# Spare_Pins.net
KiCad netlist of a schematic drawn in Altium Designer
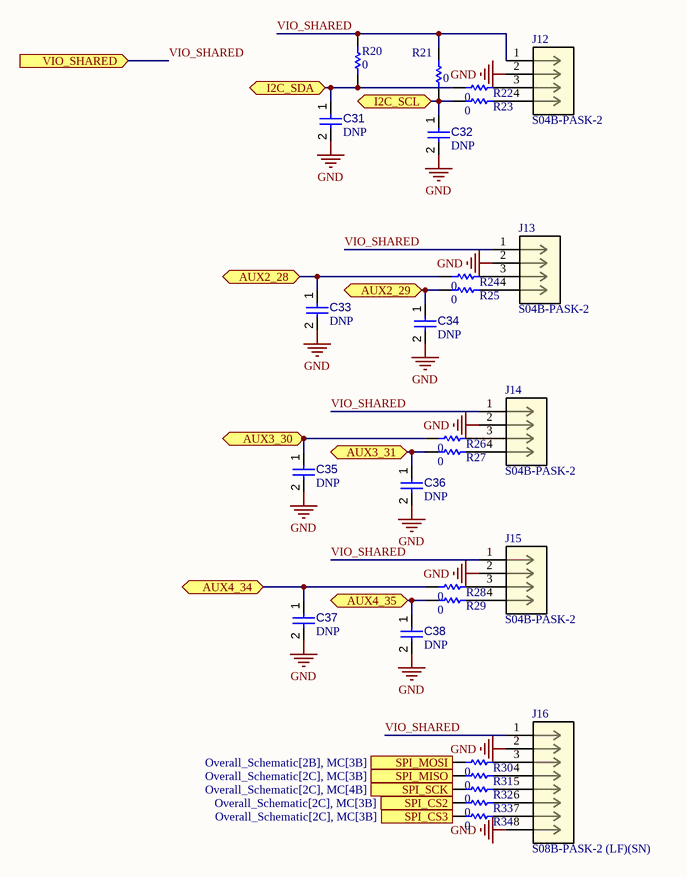
[diagram p0: Spare_Pins.SchDoc]

(export (version "E")
  (design (tool "Eeschema 10.0.6"))
  (components
    (comp (ref "C31")
      (value "DNP")
      (footprint "CAPC1608X90X40ML10T20")
      (description "0603 (1608 Metric)")
      (fields (field (name "TOLERANCE") "5%") (field (name "Comment") "DNP/placeholder"))
      (libsource (lib "Chen-Shi Liou") (part "CAP-NP-2"))
    )
    (comp (ref "C32")
      (value "DNP")
      (footprint "CAPC1608X90X40ML10T20")
      (description "0603 (1608 Metric)")
      (fields (field (name "TOLERANCE") "5%") (field (name "Comment") "DNP/placeholder"))
      (libsource (lib "Chen-Shi Liou") (part "CAP-NP-2"))
    )
    (comp (ref "C33")
      (value "DNP")
      (footprint "CAPC1608X90X40ML10T20")
      (description "0603 (1608 Metric)")
      (fields (field (name "TOLERANCE") "5%") (field (name "Comment") "DNP/placeholder"))
      (libsource (lib "Chen-Shi Liou") (part "CAP-NP-2"))
    )
    (comp (ref "C34")
      (value "DNP")
      (footprint "CAPC1608X90X40ML10T20")
      (description "0603 (1608 Metric)")
      (fields (field (name "TOLERANCE") "5%") (field (name "Comment") "DNP/placeholder"))
      (libsource (lib "Chen-Shi Liou") (part "CAP-NP-2"))
    )
    (comp (ref "C35")
      (value "DNP")
      (footprint "CAPC1608X90X40ML10T20")
      (description "0603 (1608 Metric)")
      (fields (field (name "TOLERANCE") "5%") (field (name "Comment") "DNP/placeholder"))
      (libsource (lib "Chen-Shi Liou") (part "CAP-NP-2"))
    )
    (comp (ref "C36")
      (value "DNP")
      (footprint "CAPC1608X90X40ML10T20")
      (description "0603 (1608 Metric)")
      (fields (field (name "TOLERANCE") "5%") (field (name "Comment") "DNP/placeholder"))
      (libsource (lib "Chen-Shi Liou") (part "CAP-NP-2"))
    )
    (comp (ref "C37")
      (value "DNP")
      (footprint "CAPC1608X90X40ML10T20")
      (description "0603 (1608 Metric)")
      (fields (field (name "TOLERANCE") "5%") (field (name "Comment") "DNP/placeholder"))
      (libsource (lib "Chen-Shi Liou") (part "CAP-NP-2"))
    )
    (comp (ref "C38")
      (value "DNP")
      (footprint "CAPC1608X90X40ML10T20")
      (description "0603 (1608 Metric)")
      (fields (field (name "TOLERANCE") "5%") (field (name "Comment") "DNP/placeholder"))
      (libsource (lib "Chen-Shi Liou") (part "CAP-NP-2"))
    )
    (comp (ref "J12")
      (value "S04B-PASK-2")
      (footprint "CONN4_S04B-PASK_JST")
      (description "Description")
      (fields (field (name "COPYRIGHT") "Copyright (C) 2025 Ultra Librarian. All rights reserved."))
      (libsource (lib "S04B-PASK-2") (part "S04B-PASK-2"))
    )
    (comp (ref "J13")
      (value "S04B-PASK-2")
      (footprint "CONN4_S04B-PASK_JST")
      (description "Description")
      (fields (field (name "COPYRIGHT") "Copyright (C) 2025 Ultra Librarian. All rights reserved."))
      (libsource (lib "S04B-PASK-2") (part "S04B-PASK-2"))
    )
    (comp (ref "J14")
      (value "S04B-PASK-2")
      (footprint "CONN4_S04B-PASK_JST")
      (description "Description")
      (fields (field (name "COPYRIGHT") "Copyright (C) 2025 Ultra Librarian. All rights reserved."))
      (libsource (lib "S04B-PASK-2") (part "S04B-PASK-2"))
    )
    (comp (ref "J15")
      (value "S04B-PASK-2")
      (footprint "CONN4_S04B-PASK_JST")
      (description "Description")
      (fields (field (name "COPYRIGHT") "Copyright (C) 2025 Ultra Librarian. All rights reserved."))
      (libsource (lib "S04B-PASK-2") (part "S04B-PASK-2"))
    )
    (comp (ref "J16")
      (value "S08B-PASK-2 (LF)(SN)")
      (footprint "CONN_S08B-PASK-2_JST")
      (description "Description")
      (fields (field (name "COPYRIGHT") "Copyright (C) 2026 Ultra Librarian. All rights reserved."))
      (libsource (lib "S08B-PASK-2LFSN") (part "S08B-PASK-2 LFSN"))
    )
    (comp (ref "R20")
      (value "0")
      (footprint "RESC1608X55X25ML10T15")
      (description "Chip Resistor, 0 Ohm, 0.1 W, -55 to 155 degC, 0603 (1608 Metric)")
      (fields (field (name "POWER") "100mW") (field (name "TOLERANCE") "5%"))
      (libsource (lib "Chen-Shi Liou") (part "RES-2"))
    )
    (comp (ref "R21")
      (value "0")
      (footprint "RESC1608X55X25ML10T15")
      (description "Chip Resistor, 0 Ohm, 0.1 W, -55 to 155 degC, 0603 (1608 Metric)")
      (fields (field (name "POWER") "100mW") (field (name "TOLERANCE") "5%"))
      (libsource (lib "Chen-Shi Liou") (part "RES-2"))
    )
    (comp (ref "R22")
      (value "0")
      (footprint "RESC1608X55X25ML10T15")
      (description "Chip Resistor, 0 Ohm, 0.1 W, -55 to 155 degC, 0603 (1608 Metric)")
      (fields (field (name "POWER") "100mW") (field (name "TOLERANCE") "5%"))
      (libsource (lib "Chen-Shi Liou") (part "RES-2"))
    )
    (comp (ref "R23")
      (value "0")
      (footprint "RESC1608X55X25ML10T15")
      (description "Chip Resistor, 0 Ohm, 0.1 W, -55 to 155 degC, 0603 (1608 Metric)")
      (fields (field (name "POWER") "100mW") (field (name "TOLERANCE") "5%"))
      (libsource (lib "Chen-Shi Liou") (part "RES-2"))
    )
    (comp (ref "R24")
      (value "0")
      (footprint "RESC1608X55X25ML10T15")
      (description "Chip Resistor, 0 Ohm, 0.1 W, -55 to 155 degC, 0603 (1608 Metric)")
      (fields (field (name "POWER") "100mW") (field (name "TOLERANCE") "5%"))
      (libsource (lib "Chen-Shi Liou") (part "RES-2"))
    )
    (comp (ref "R25")
      (value "0")
      (footprint "RESC1608X55X25ML10T15")
      (description "Chip Resistor, 0 Ohm, 0.1 W, -55 to 155 degC, 0603 (1608 Metric)")
      (fields (field (name "POWER") "100mW") (field (name "TOLERANCE") "5%"))
      (libsource (lib "Chen-Shi Liou") (part "RES-2"))
    )
    (comp (ref "R26")
      (value "0")
      (footprint "RESC1608X55X25ML10T15")
      (description "Chip Resistor, 0 Ohm, 0.1 W, -55 to 155 degC, 0603 (1608 Metric)")
      (fields (field (name "POWER") "100mW") (field (name "TOLERANCE") "5%"))
      (libsource (lib "Chen-Shi Liou") (part "RES-2"))
    )
    (comp (ref "R27")
      (value "0")
      (footprint "RESC1608X55X25ML10T15")
      (description "Chip Resistor, 0 Ohm, 0.1 W, -55 to 155 degC, 0603 (1608 Metric)")
      (fields (field (name "POWER") "100mW") (field (name "TOLERANCE") "5%"))
      (libsource (lib "Chen-Shi Liou") (part "RES-2"))
    )
    (comp (ref "R28")
      (value "0")
      (footprint "RESC1608X55X25ML10T15")
      (description "Chip Resistor, 0 Ohm, 0.1 W, -55 to 155 degC, 0603 (1608 Metric)")
      (fields (field (name "POWER") "100mW") (field (name "TOLERANCE") "5%"))
      (libsource (lib "Chen-Shi Liou") (part "RES-2"))
    )
    (comp (ref "R29")
      (value "0")
      (footprint "RESC1608X55X25ML10T15")
      (description "Chip Resistor, 0 Ohm, 0.1 W, -55 to 155 degC, 0603 (1608 Metric)")
      (fields (field (name "POWER") "100mW") (field (name "TOLERANCE") "5%"))
      (libsource (lib "Chen-Shi Liou") (part "RES-2"))
    )
    (comp (ref "R30")
      (value "0")
      (footprint "RESC1608X55X25ML10T15")
      (description "Chip Resistor, 0 Ohm, 0.1 W, -55 to 155 degC, 0603 (1608 Metric)")
      (fields (field (name "POWER") "100mW") (field (name "TOLERANCE") "5%"))
      (libsource (lib "Chen-Shi Liou") (part "RES-2"))
    )
    (comp (ref "R31")
      (value "0")
      (footprint "RESC1608X55X25ML10T15")
      (description "Chip Resistor, 0 Ohm, 0.1 W, -55 to 155 degC, 0603 (1608 Metric)")
      (fields (field (name "POWER") "100mW") (field (name "TOLERANCE") "5%"))
      (libsource (lib "Chen-Shi Liou") (part "RES-2"))
    )
    (comp (ref "R32")
      (value "0")
      (footprint "RESC1608X55X25ML10T15")
      (description "Chip Resistor, 0 Ohm, 0.1 W, -55 to 155 degC, 0603 (1608 Metric)")
      (fields (field (name "POWER") "100mW") (field (name "TOLERANCE") "5%"))
      (libsource (lib "Chen-Shi Liou") (part "RES-2"))
    )
    (comp (ref "R33")
      (value "0")
      (footprint "RESC1608X55X25ML10T15")
      (description "Chip Resistor, 0 Ohm, 0.1 W, -55 to 155 degC, 0603 (1608 Metric)")
      (fields (field (name "POWER") "100mW") (field (name "TOLERANCE") "5%"))
      (libsource (lib "Chen-Shi Liou") (part "RES-2"))
    )
    (comp (ref "R34")
      (value "0")
      (footprint "RESC1608X55X25ML10T15")
      (description "Chip Resistor, 0 Ohm, 0.1 W, -55 to 155 degC, 0603 (1608 Metric)")
      (fields (field (name "POWER") "100mW") (field (name "TOLERANCE") "5%"))
      (libsource (lib "Chen-Shi Liou") (part "RES-2"))
    )
  )
  (nets
    (net (code "1") (name "/AUX2_28") (class "Default")
      (node (ref "C33") (pin "1") (pinfunction "1_1") (pintype "passive"))
      (node (ref "R24") (pin "1") (pinfunction "1_1") (pintype "passive"))
    )
    (net (code "2") (name "/AUX2_29") (class "Default")
      (node (ref "C34") (pin "1") (pinfunction "1_1") (pintype "passive"))
      (node (ref "R25") (pin "1") (pinfunction "1_1") (pintype "passive"))
    )
    (net (code "3") (name "/AUX3_30") (class "Default")
      (node (ref "C35") (pin "1") (pinfunction "1_1") (pintype "passive"))
      (node (ref "R26") (pin "1") (pinfunction "1_1") (pintype "passive"))
    )
    (net (code "4") (name "/AUX3_31") (class "Default")
      (node (ref "C36") (pin "1") (pinfunction "1_1") (pintype "passive"))
      (node (ref "R27") (pin "1") (pinfunction "1_1") (pintype "passive"))
    )
    (net (code "5") (name "/AUX4_34") (class "Default")
      (node (ref "C37") (pin "1") (pinfunction "1_1") (pintype "passive"))
      (node (ref "R28") (pin "1") (pinfunction "1_1") (pintype "passive"))
    )
    (net (code "6") (name "/AUX4_35") (class "Default")
      (node (ref "C38") (pin "1") (pinfunction "1_1") (pintype "passive"))
      (node (ref "R29") (pin "1") (pinfunction "1_1") (pintype "passive"))
    )
    (net (code "7") (name "/I2C_SCL") (class "Default")
      (node (ref "C32") (pin "1") (pinfunction "1_1") (pintype "passive"))
      (node (ref "R21") (pin "1") (pinfunction "1_1") (pintype "passive"))
      (node (ref "R23") (pin "1") (pinfunction "1_1") (pintype "passive"))
    )
    (net (code "8") (name "/I2C_SDA") (class "Default")
      (node (ref "C31") (pin "1") (pinfunction "1_1") (pintype "passive"))
      (node (ref "R20") (pin "1") (pinfunction "1_1") (pintype "passive"))
      (node (ref "R22") (pin "1") (pinfunction "1_1") (pintype "passive"))
    )
    (net (code "9") (name "/SPI_CS2") (class "Default")
      (node (ref "R33") (pin "1") (pinfunction "1_1") (pintype "passive"))
    )
    (net (code "10") (name "/SPI_CS3") (class "Default")
      (node (ref "R34") (pin "1") (pinfunction "1_1") (pintype "passive"))
    )
    (net (code "11") (name "/SPI_MISO") (class "Default")
      (node (ref "R31") (pin "1") (pinfunction "1_1") (pintype "passive"))
    )
    (net (code "12") (name "/SPI_MOSI") (class "Default")
      (node (ref "R30") (pin "1") (pinfunction "1_1") (pintype "passive"))
    )
    (net (code "13") (name "/SPI_SCK") (class "Default")
      (node (ref "R32") (pin "1") (pinfunction "1_1") (pintype "passive"))
    )
    (net (code "14") (name "/VIO_SHARED") (class "Default")
      (node (ref "J12") (pin "1") (pinfunction "1_1") (pintype "passive"))
      (node (ref "J13") (pin "1") (pinfunction "1_1") (pintype "passive"))
      (node (ref "J14") (pin "1") (pinfunction "1_1") (pintype "passive"))
      (node (ref "J15") (pin "1") (pinfunction "1_1") (pintype "passive"))
      (node (ref "J16") (pin "1") (pinfunction "1_1") (pintype "passive"))
      (node (ref "R20") (pin "2") (pinfunction "2_2") (pintype "passive"))
      (node (ref "R21") (pin "2") (pinfunction "2_2") (pintype "passive"))
    )
    (net (code "15") (name "GND") (class "Default")
      (node (ref "C31") (pin "2") (pinfunction "2_2") (pintype "passive"))
      (node (ref "C32") (pin "2") (pinfunction "2_2") (pintype "passive"))
      (node (ref "C33") (pin "2") (pinfunction "2_2") (pintype "passive"))
      (node (ref "C34") (pin "2") (pinfunction "2_2") (pintype "passive"))
      (node (ref "C35") (pin "2") (pinfunction "2_2") (pintype "passive"))
      (node (ref "C36") (pin "2") (pinfunction "2_2") (pintype "passive"))
      (node (ref "C37") (pin "2") (pinfunction "2_2") (pintype "passive"))
      (node (ref "C38") (pin "2") (pinfunction "2_2") (pintype "passive"))
      (node (ref "J12") (pin "2") (pinfunction "2_2") (pintype "passive"))
      (node (ref "J13") (pin "2") (pinfunction "2_2") (pintype "passive"))
      (node (ref "J14") (pin "2") (pinfunction "2_2") (pintype "passive"))
      (node (ref "J15") (pin "2") (pinfunction "2_2") (pintype "passive"))
      (node (ref "J16") (pin "2") (pinfunction "2_2") (pintype "passive"))
      (node (ref "J16") (pin "8") (pinfunction "8_8") (pintype "passive"))
    )
    (net (code "16") (name "Net-(J12-Pad3)") (class "Default")
      (node (ref "J12") (pin "3") (pinfunction "3_3") (pintype "passive"))
      (node (ref "R22") (pin "2") (pinfunction "2_2") (pintype "passive"))
    )
    (net (code "17") (name "Net-(J12-Pad4)") (class "Default")
      (node (ref "J12") (pin "4") (pinfunction "4_4") (pintype "passive"))
      (node (ref "R23") (pin "2") (pinfunction "2_2") (pintype "passive"))
    )
    (net (code "18") (name "Net-(J13-Pad3)") (class "Default")
      (node (ref "J13") (pin "3") (pinfunction "3_3") (pintype "passive"))
      (node (ref "R24") (pin "2") (pinfunction "2_2") (pintype "passive"))
    )
    (net (code "19") (name "Net-(J13-Pad4)") (class "Default")
      (node (ref "J13") (pin "4") (pinfunction "4_4") (pintype "passive"))
      (node (ref "R25") (pin "2") (pinfunction "2_2") (pintype "passive"))
    )
    (net (code "20") (name "Net-(J14-Pad3)") (class "Default")
      (node (ref "J14") (pin "3") (pinfunction "3_3") (pintype "passive"))
      (node (ref "R26") (pin "2") (pinfunction "2_2") (pintype "passive"))
    )
    (net (code "21") (name "Net-(J14-Pad4)") (class "Default")
      (node (ref "J14") (pin "4") (pinfunction "4_4") (pintype "passive"))
      (node (ref "R27") (pin "2") (pinfunction "2_2") (pintype "passive"))
    )
    (net (code "22") (name "Net-(J15-Pad3)") (class "Default")
      (node (ref "J15") (pin "3") (pinfunction "3_3") (pintype "passive"))
      (node (ref "R28") (pin "2") (pinfunction "2_2") (pintype "passive"))
    )
    (net (code "23") (name "Net-(J15-Pad4)") (class "Default")
      (node (ref "J15") (pin "4") (pinfunction "4_4") (pintype "passive"))
      (node (ref "R29") (pin "2") (pinfunction "2_2") (pintype "passive"))
    )
    (net (code "24") (name "Net-(J16-Pad3)") (class "Default")
      (node (ref "J16") (pin "3") (pinfunction "3_3") (pintype "passive"))
      (node (ref "R30") (pin "2") (pinfunction "2_2") (pintype "passive"))
    )
    (net (code "25") (name "Net-(J16-Pad4)") (class "Default")
      (node (ref "J16") (pin "4") (pinfunction "4_4") (pintype "passive"))
      (node (ref "R31") (pin "2") (pinfunction "2_2") (pintype "passive"))
    )
    (net (code "26") (name "Net-(J16-Pad5)") (class "Default")
      (node (ref "J16") (pin "5") (pinfunction "5_5") (pintype "passive"))
      (node (ref "R32") (pin "2") (pinfunction "2_2") (pintype "passive"))
    )
    (net (code "27") (name "Net-(J16-Pad6)") (class "Default")
      (node (ref "J16") (pin "6") (pinfunction "6_6") (pintype "passive"))
      (node (ref "R33") (pin "2") (pinfunction "2_2") (pintype "passive"))
    )
    (net (code "28") (name "Net-(J16-Pad7)") (class "Default")
      (node (ref "J16") (pin "7") (pinfunction "7_7") (pintype "passive"))
      (node (ref "R34") (pin "2") (pinfunction "2_2") (pintype "passive"))
    )
  )
)
